# SCH_FMC-R2_MBOT_2026-02-22.net
KiCad netlist of a schematic drawn in EasyEDA
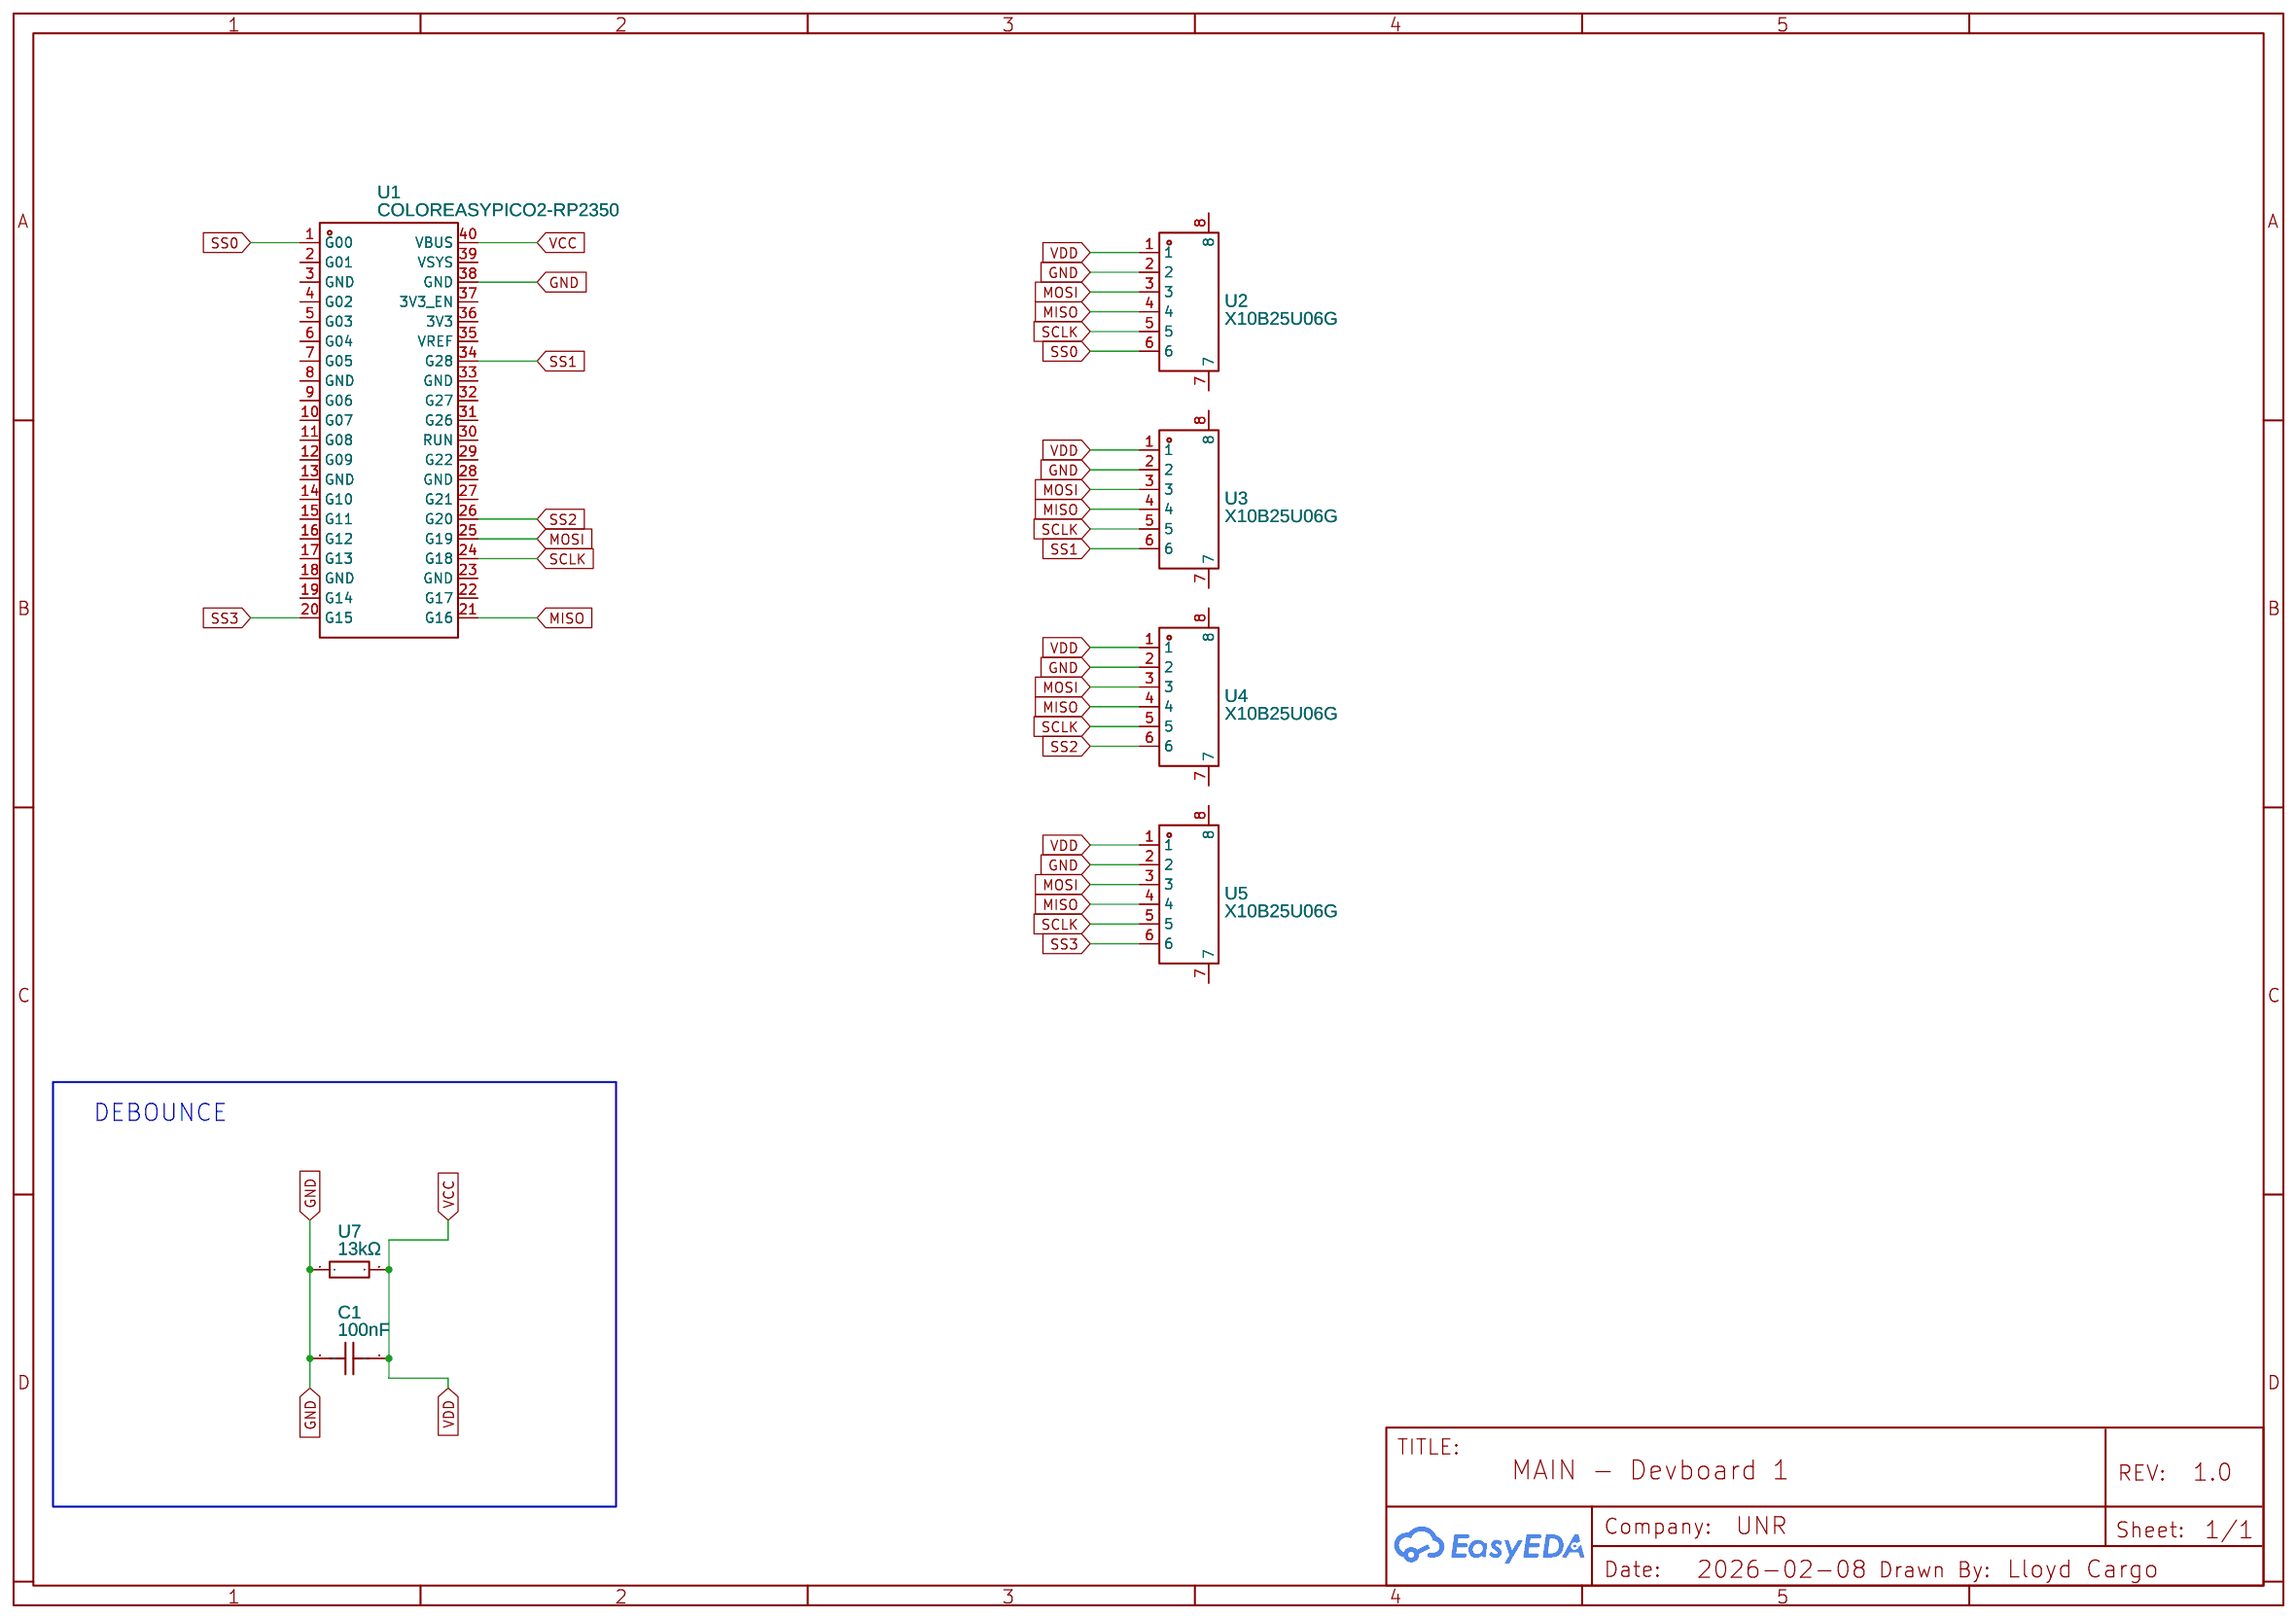
[diagram p0: MAIN]
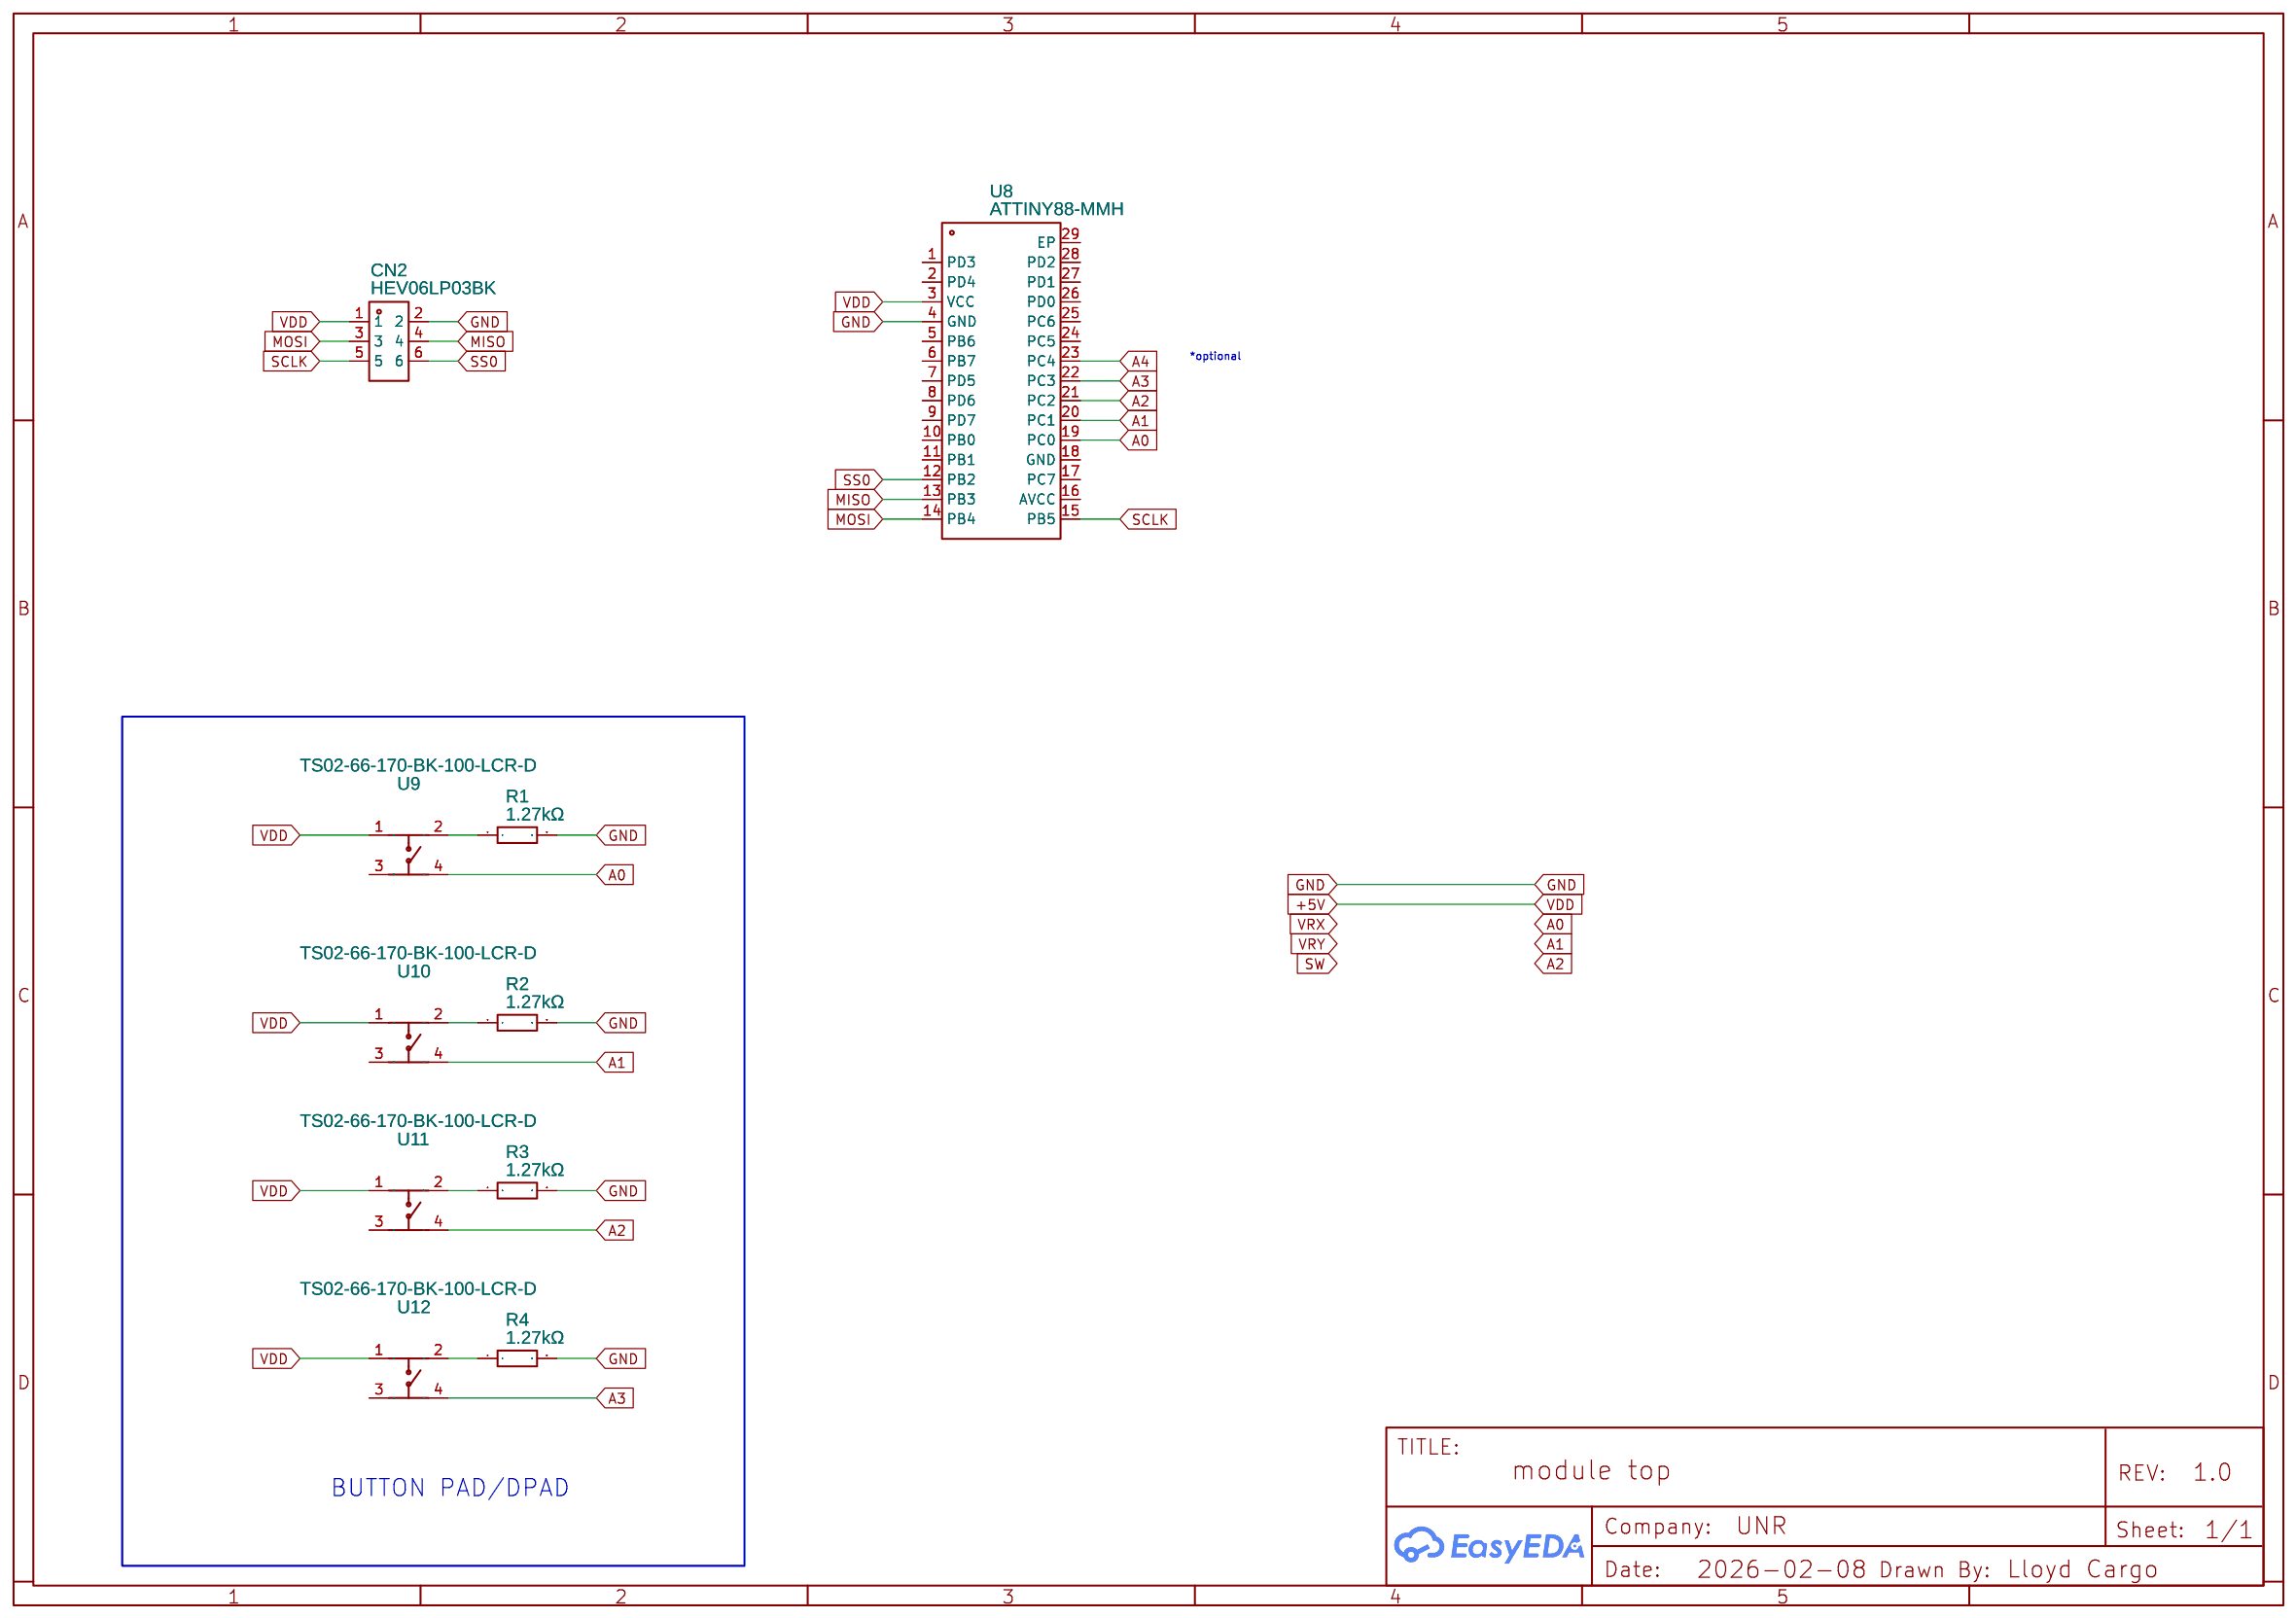
[diagram p1: module top]
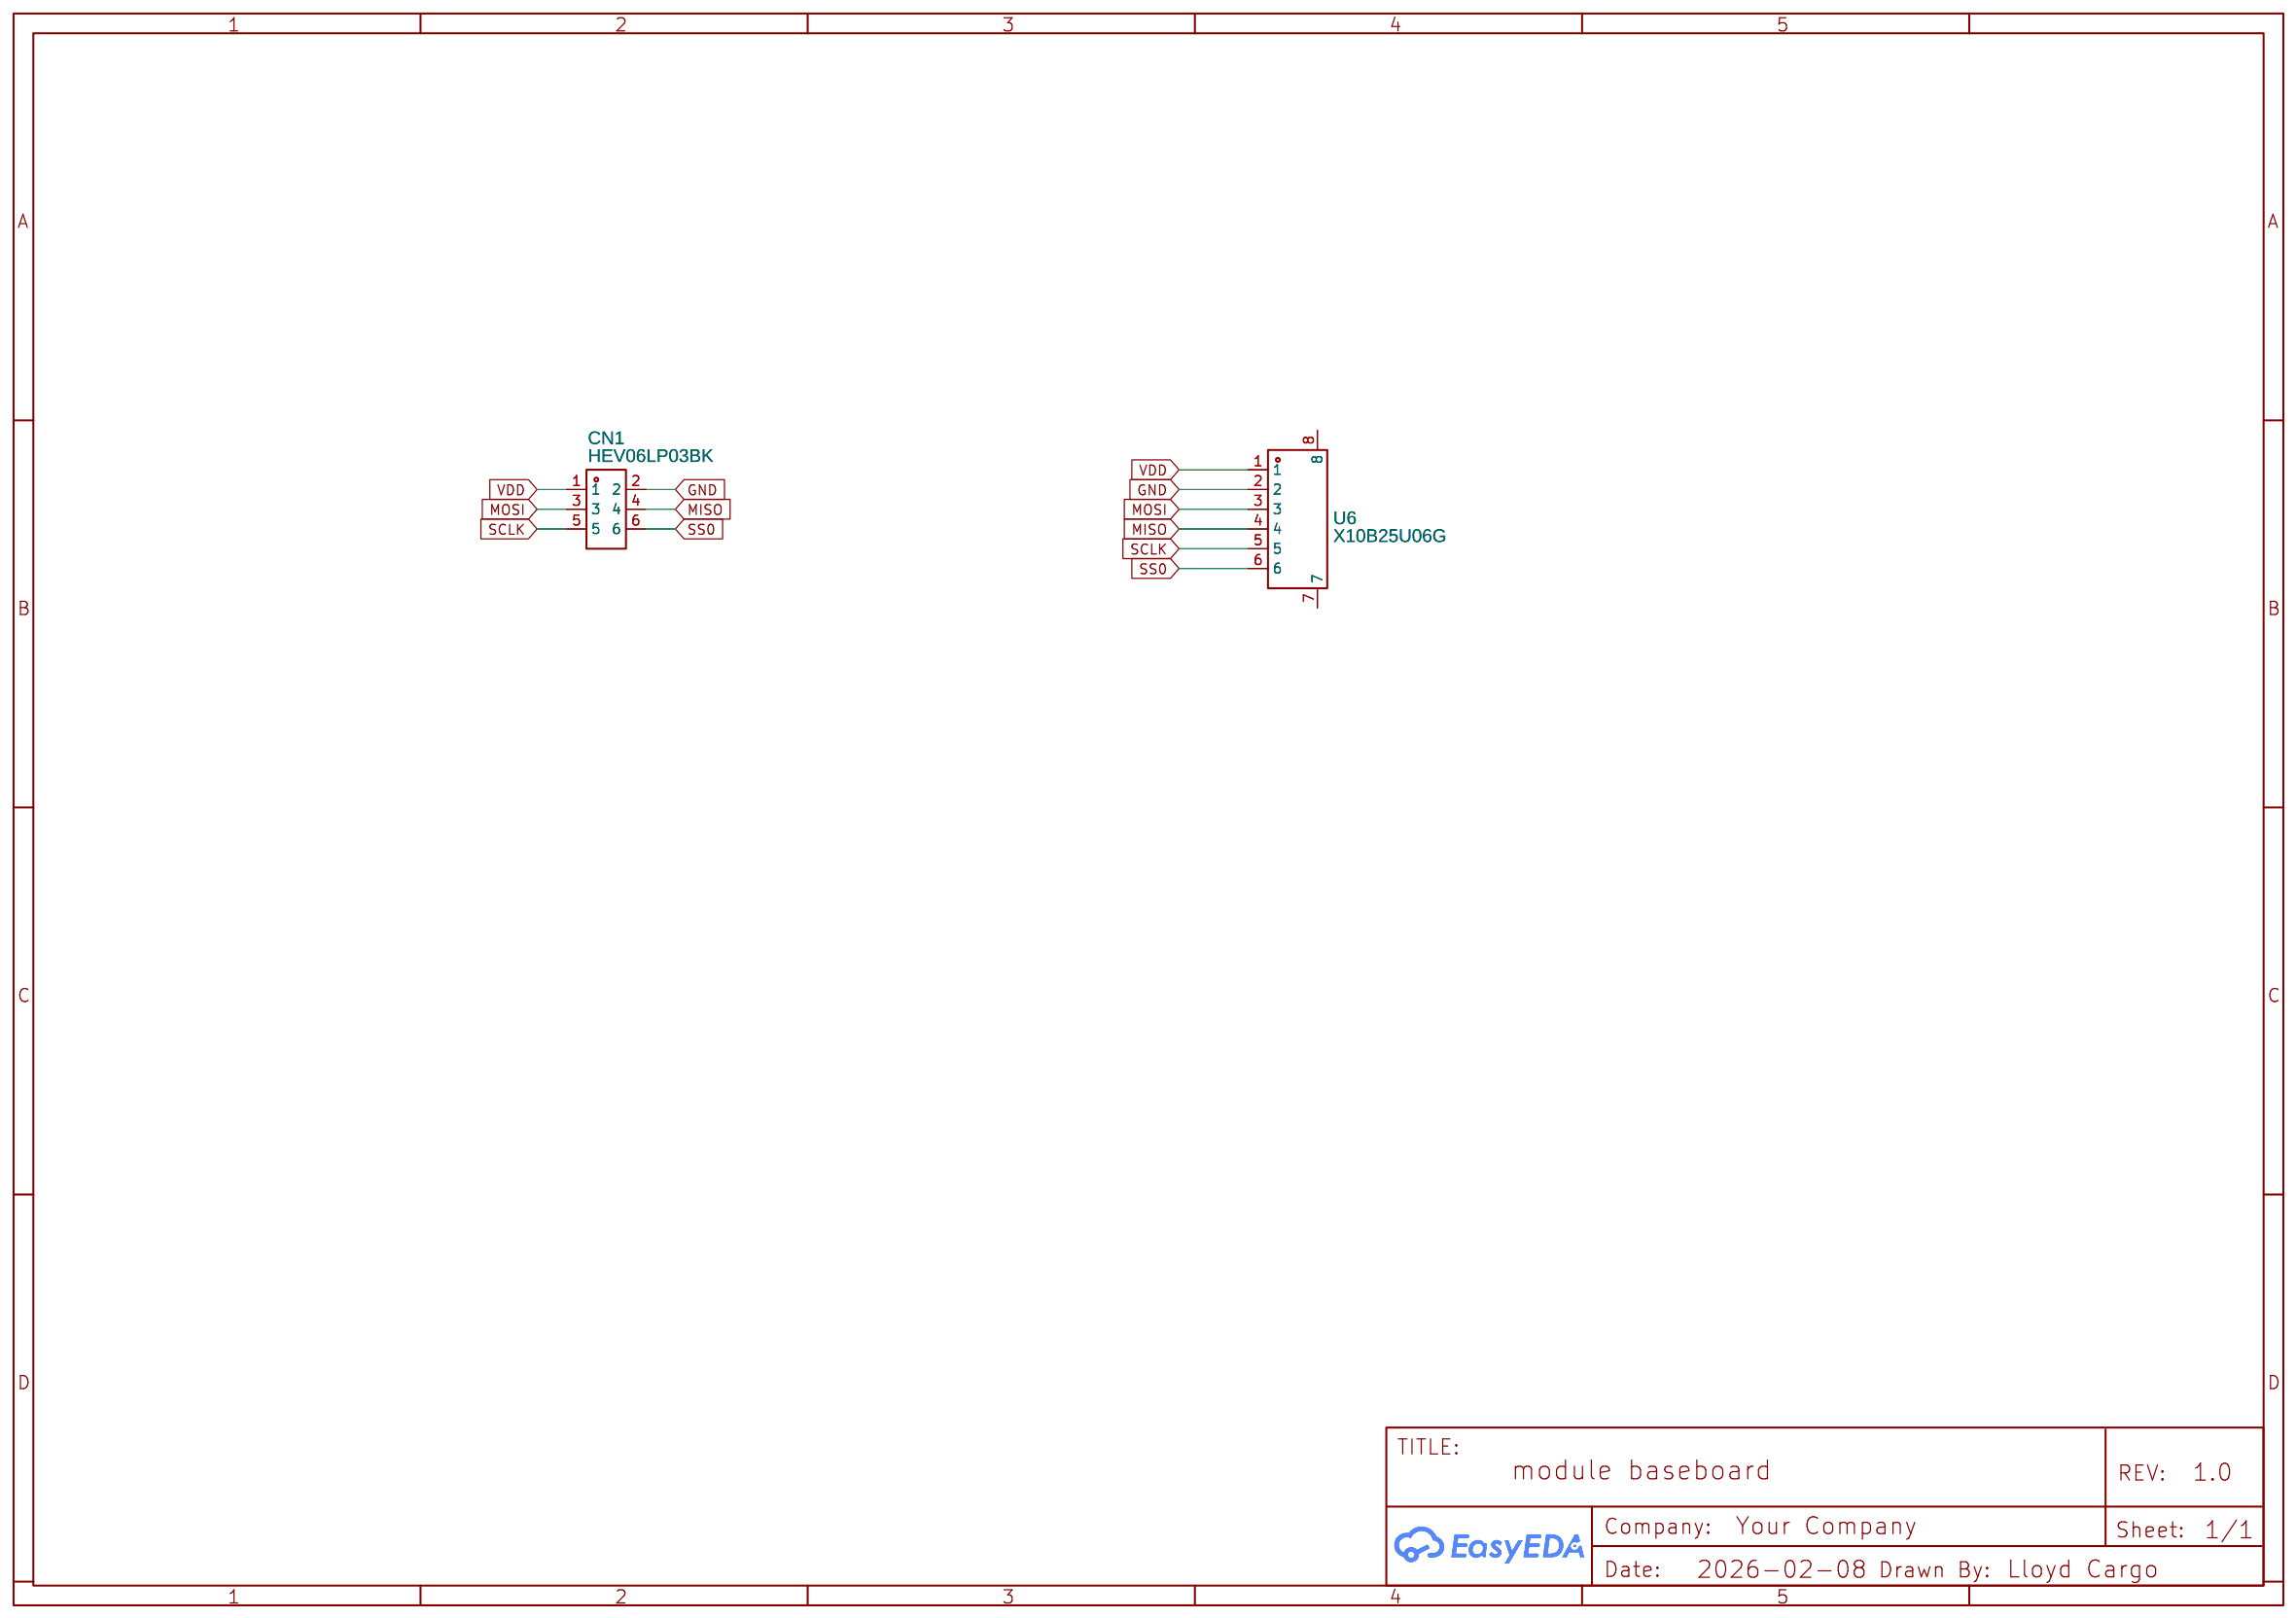
[diagram p2: module baseboard]

(export (version "E")
  (design (tool "Eeschema 10.0.6"))
  (components
    (comp (ref "C1")
      (value "100nF")
      (fields
        (field (name "Manufacturer Part") "GCG188R92A104KA03D")
        (field (name "Manufacturer") "muRata(村田)")
      )
      (libsource (lib "") (part "GCG188R92A104KA03D"))
    )
    (comp (ref "U1")
      (value "COLOREASYPICO2-RP2350")
      (fields
        (field (name "Manufacturer Part") "ColorEasyPico2-RP2350")
        (field (name "Manufacturer") "立创开发板")
      )
      (libsource (lib "") (part "COLOREASYPICO2-RP2350"))
    )
    (comp (ref "U2")
      (value "X10B25U06G")
      (fields (field (name "Manufacturer") "XKB Connection(中国星坤)"))
      (libsource (lib "") (part "X10B25U06G"))
    )
    (comp (ref "U3")
      (value "X10B25U06G")
      (fields (field (name "Manufacturer") "XKB Connection(中国星坤)"))
      (libsource (lib "") (part "X10B25U06G"))
    )
    (comp (ref "U4")
      (value "X10B25U06G")
      (fields (field (name "Manufacturer") "XKB Connection(中国星坤)"))
      (libsource (lib "") (part "X10B25U06G"))
    )
    (comp (ref "U5")
      (value "X10B25U06G")
      (fields (field (name "Manufacturer") "XKB Connection(中国星坤)"))
      (libsource (lib "") (part "X10B25U06G"))
    )
    (comp (ref "U7")
      (value "13kΩ")
      (fields (field (name "Manufacturer Part") "HPCR0805F13K0K9") (field (name "Manufacturer") "RESI(开步睿思)"))
      (libsource (lib "") (part "HPCR0805F13K0K9"))
    )
    (comp (ref "CN2")
      (value "HEV06LP03BK")
      (fields (field (name "Manufacturer") "WingTAT(格林柏)"))
      (libsource (lib "") (part "HEV06LP03BK"))
    )
    (comp (ref "R1")
      (value "1.27kΩ")
      (fields (field (name "Manufacturer Part") "RC0603FR-071K27L") (field (name "Manufacturer") "YAGEO(国巨)"))
      (libsource (lib "") (part "RC0603FR-071K27L"))
    )
    (comp (ref "R2")
      (value "1.27kΩ")
      (fields (field (name "Manufacturer Part") "RC0603FR-071K27L") (field (name "Manufacturer") "YAGEO(国巨)"))
      (libsource (lib "") (part "RC0603FR-071K27L"))
    )
    (comp (ref "R3")
      (value "1.27kΩ")
      (fields (field (name "Manufacturer Part") "RC0603FR-071K27L") (field (name "Manufacturer") "YAGEO(国巨)"))
      (libsource (lib "") (part "RC0603FR-071K27L"))
    )
    (comp (ref "R4")
      (value "1.27kΩ")
      (fields (field (name "Manufacturer Part") "RC0603FR-071K27L") (field (name "Manufacturer") "YAGEO(国巨)"))
      (libsource (lib "") (part "RC0603FR-071K27L"))
    )
    (comp (ref "U8")
      (value "ATTINY88-MMH")
      (fields (field (name "Manufacturer") "MICROCHIP(美国微芯)"))
      (libsource (lib "") (part "ATTINY88-MMH"))
    )
    (comp (ref "U9")
      (value "TS02-66-170-BK-100-LCR-D")
      (fields (field (name "Manufacturer") "CUI"))
      (libsource (lib "") (part "TS02-66-170-BK-100-LCR-D"))
    )
    (comp (ref "U10")
      (value "TS02-66-170-BK-100-LCR-D")
      (fields (field (name "Manufacturer") "CUI"))
      (libsource (lib "") (part "TS02-66-170-BK-100-LCR-D"))
    )
    (comp (ref "U11")
      (value "TS02-66-170-BK-100-LCR-D")
      (fields (field (name "Manufacturer") "CUI"))
      (libsource (lib "") (part "TS02-66-170-BK-100-LCR-D"))
    )
    (comp (ref "U12")
      (value "TS02-66-170-BK-100-LCR-D")
      (fields (field (name "Manufacturer") "CUI"))
      (libsource (lib "") (part "TS02-66-170-BK-100-LCR-D"))
    )
    (comp (ref "CN1")
      (value "HEV06LP03BK")
      (fields (field (name "Manufacturer") "WingTAT(格林柏)"))
      (libsource (lib "") (part "HEV06LP03BK"))
    )
    (comp (ref "U6")
      (value "X10B25U06G")
      (fields (field (name "Manufacturer") "XKB Connection(中国星坤)"))
      (libsource (lib "") (part "X10B25U06G"))
    )
  )
  (nets
    (net (code "1") (name "+5V") (class "Default")
      (node (ref "C1") (pin "2") (pinfunction "2_2") (pintype "unspecified"))
      (node (ref "CN1") (pin "1") (pinfunction "1_1") (pintype "unspecified"))
      (node (ref "CN2") (pin "1") (pinfunction "1_1") (pintype "unspecified"))
      (node (ref "U1") (pin "40") (pinfunction "VBUS_40") (pintype "unspecified"))
      (node (ref "U10") (pin "1") (pinfunction "1_1") (pintype "unspecified"))
      (node (ref "U11") (pin "1") (pinfunction "1_1") (pintype "unspecified"))
      (node (ref "U12") (pin "1") (pinfunction "1_1") (pintype "unspecified"))
      (node (ref "U2") (pin "1") (pinfunction "1_1") (pintype "unspecified"))
      (node (ref "U3") (pin "1") (pinfunction "1_1") (pintype "unspecified"))
      (node (ref "U4") (pin "1") (pinfunction "1_1") (pintype "unspecified"))
      (node (ref "U5") (pin "1") (pinfunction "1_1") (pintype "unspecified"))
      (node (ref "U6") (pin "1") (pinfunction "1_1") (pintype "unspecified"))
      (node (ref "U7") (pin "2") (pinfunction "2_2") (pintype "unspecified"))
      (node (ref "U8") (pin "3") (pinfunction "VCC_3") (pintype "unspecified"))
      (node (ref "U9") (pin "1") (pinfunction "1_1") (pintype "unspecified"))
    )
    (net (code "2") (name "A0") (class "Default")
      (node (ref "U8") (pin "19") (pinfunction "PC0_19") (pintype "unspecified"))
      (node (ref "U9") (pin "4") (pinfunction "4_4") (pintype "unspecified"))
    )
    (net (code "3") (name "A1") (class "Default")
      (node (ref "U10") (pin "4") (pinfunction "4_4") (pintype "unspecified"))
      (node (ref "U8") (pin "20") (pinfunction "PC1_20") (pintype "unspecified"))
    )
    (net (code "4") (name "A2") (class "Default")
      (node (ref "U11") (pin "4") (pinfunction "4_4") (pintype "unspecified"))
      (node (ref "U8") (pin "21") (pinfunction "PC2_21") (pintype "unspecified"))
    )
    (net (code "5") (name "A3") (class "Default")
      (node (ref "U12") (pin "4") (pinfunction "4_4") (pintype "unspecified"))
      (node (ref "U8") (pin "22") (pinfunction "PC3_22") (pintype "unspecified"))
    )
    (net (code "6") (name "A4") (class "Default")
      (node (ref "U8") (pin "23") (pinfunction "PC4_23") (pintype "unspecified"))
    )
    (net (code "7") (name "GND") (class "Default")
      (node (ref "C1") (pin "1") (pinfunction "1_1") (pintype "unspecified"))
      (node (ref "CN1") (pin "2") (pinfunction "2_2") (pintype "unspecified"))
      (node (ref "CN2") (pin "2") (pinfunction "2_2") (pintype "unspecified"))
      (node (ref "R1") (pin "2") (pinfunction "2_2") (pintype "unspecified"))
      (node (ref "R2") (pin "2") (pinfunction "2_2") (pintype "unspecified"))
      (node (ref "R3") (pin "2") (pinfunction "2_2") (pintype "unspecified"))
      (node (ref "R4") (pin "2") (pinfunction "2_2") (pintype "unspecified"))
      (node (ref "U1") (pin "38") (pinfunction "GND_38") (pintype "unspecified"))
      (node (ref "U2") (pin "2") (pinfunction "2_2") (pintype "unspecified"))
      (node (ref "U3") (pin "2") (pinfunction "2_2") (pintype "unspecified"))
      (node (ref "U4") (pin "2") (pinfunction "2_2") (pintype "unspecified"))
      (node (ref "U5") (pin "2") (pinfunction "2_2") (pintype "unspecified"))
      (node (ref "U6") (pin "2") (pinfunction "2_2") (pintype "unspecified"))
      (node (ref "U7") (pin "1") (pinfunction "1_1") (pintype "unspecified"))
      (node (ref "U8") (pin "4") (pinfunction "GND_4") (pintype "unspecified"))
    )
    (net (code "8") (name "MISO") (class "Default")
      (node (ref "CN1") (pin "4") (pinfunction "4_4") (pintype "unspecified"))
      (node (ref "CN2") (pin "4") (pinfunction "4_4") (pintype "unspecified"))
      (node (ref "U1") (pin "21") (pinfunction "G16_21") (pintype "unspecified"))
      (node (ref "U2") (pin "4") (pinfunction "4_4") (pintype "unspecified"))
      (node (ref "U3") (pin "4") (pinfunction "4_4") (pintype "unspecified"))
      (node (ref "U4") (pin "4") (pinfunction "4_4") (pintype "unspecified"))
      (node (ref "U5") (pin "4") (pinfunction "4_4") (pintype "unspecified"))
      (node (ref "U6") (pin "4") (pinfunction "4_4") (pintype "unspecified"))
      (node (ref "U8") (pin "13") (pinfunction "PB3_13") (pintype "unspecified"))
    )
    (net (code "9") (name "MOSI") (class "Default")
      (node (ref "CN1") (pin "3") (pinfunction "3_3") (pintype "unspecified"))
      (node (ref "CN2") (pin "3") (pinfunction "3_3") (pintype "unspecified"))
      (node (ref "U1") (pin "25") (pinfunction "G19_25") (pintype "unspecified"))
      (node (ref "U2") (pin "3") (pinfunction "3_3") (pintype "unspecified"))
      (node (ref "U3") (pin "3") (pinfunction "3_3") (pintype "unspecified"))
      (node (ref "U4") (pin "3") (pinfunction "3_3") (pintype "unspecified"))
      (node (ref "U5") (pin "3") (pinfunction "3_3") (pintype "unspecified"))
      (node (ref "U6") (pin "3") (pinfunction "3_3") (pintype "unspecified"))
      (node (ref "U8") (pin "14") (pinfunction "PB4_14") (pintype "unspecified"))
    )
    (net (code "10") (name "Net-(R1-Pad1)") (class "Default")
      (node (ref "R1") (pin "1") (pinfunction "1_1") (pintype "unspecified"))
      (node (ref "U9") (pin "2") (pinfunction "2_2") (pintype "unspecified"))
    )
    (net (code "11") (name "Net-(R2-Pad1)") (class "Default")
      (node (ref "R2") (pin "1") (pinfunction "1_1") (pintype "unspecified"))
      (node (ref "U10") (pin "2") (pinfunction "2_2") (pintype "unspecified"))
    )
    (net (code "12") (name "Net-(R3-Pad1)") (class "Default")
      (node (ref "R3") (pin "1") (pinfunction "1_1") (pintype "unspecified"))
      (node (ref "U11") (pin "2") (pinfunction "2_2") (pintype "unspecified"))
    )
    (net (code "13") (name "Net-(R4-Pad1)") (class "Default")
      (node (ref "R4") (pin "1") (pinfunction "1_1") (pintype "unspecified"))
      (node (ref "U12") (pin "2") (pinfunction "2_2") (pintype "unspecified"))
    )
    (net (code "14") (name "SCLK") (class "Default")
      (node (ref "CN1") (pin "5") (pinfunction "5_5") (pintype "unspecified"))
      (node (ref "CN2") (pin "5") (pinfunction "5_5") (pintype "unspecified"))
      (node (ref "U1") (pin "24") (pinfunction "G18_24") (pintype "unspecified"))
      (node (ref "U2") (pin "5") (pinfunction "5_5") (pintype "unspecified"))
      (node (ref "U3") (pin "5") (pinfunction "5_5") (pintype "unspecified"))
      (node (ref "U4") (pin "5") (pinfunction "5_5") (pintype "unspecified"))
      (node (ref "U5") (pin "5") (pinfunction "5_5") (pintype "unspecified"))
      (node (ref "U6") (pin "5") (pinfunction "5_5") (pintype "unspecified"))
      (node (ref "U8") (pin "15") (pinfunction "PB5_15") (pintype "unspecified"))
    )
    (net (code "15") (name "SS0") (class "Default")
      (node (ref "CN1") (pin "6") (pinfunction "6_6") (pintype "unspecified"))
      (node (ref "CN2") (pin "6") (pinfunction "6_6") (pintype "unspecified"))
      (node (ref "U1") (pin "1") (pinfunction "G00_1") (pintype "unspecified"))
      (node (ref "U2") (pin "6") (pinfunction "6_6") (pintype "unspecified"))
      (node (ref "U6") (pin "6") (pinfunction "6_6") (pintype "unspecified"))
      (node (ref "U8") (pin "12") (pinfunction "PB2_12") (pintype "unspecified"))
    )
    (net (code "16") (name "SS1") (class "Default")
      (node (ref "U1") (pin "34") (pinfunction "G28_34") (pintype "unspecified"))
      (node (ref "U3") (pin "6") (pinfunction "6_6") (pintype "unspecified"))
    )
    (net (code "17") (name "SS2") (class "Default")
      (node (ref "U1") (pin "26") (pinfunction "G20_26") (pintype "unspecified"))
      (node (ref "U4") (pin "6") (pinfunction "6_6") (pintype "unspecified"))
    )
    (net (code "18") (name "SS3") (class "Default")
      (node (ref "U1") (pin "20") (pinfunction "G15_20") (pintype "unspecified"))
      (node (ref "U5") (pin "6") (pinfunction "6_6") (pintype "unspecified"))
    )
    (net (code "22") (name "unconnected-(U1-3V3-Pad36)") (class "Default")
      (node (ref "U1") (pin "36") (pinfunction "3V3_36") (pintype "unspecified"))
    )
    (net (code "23") (name "unconnected-(U1-3V3_EN-Pad37)") (class "Default")
      (node (ref "U1") (pin "37") (pinfunction "3V3_EN_37") (pintype "unspecified"))
    )
    (net (code "24") (name "unconnected-(U1-G01-Pad2)") (class "Default")
      (node (ref "U1") (pin "2") (pinfunction "G01_2") (pintype "unspecified"))
    )
    (net (code "25") (name "unconnected-(U1-G02-Pad4)") (class "Default")
      (node (ref "U1") (pin "4") (pinfunction "G02_4") (pintype "unspecified"))
    )
    (net (code "26") (name "unconnected-(U1-G03-Pad5)") (class "Default")
      (node (ref "U1") (pin "5") (pinfunction "G03_5") (pintype "unspecified"))
    )
    (net (code "27") (name "unconnected-(U1-G04-Pad6)") (class "Default")
      (node (ref "U1") (pin "6") (pinfunction "G04_6") (pintype "unspecified"))
    )
    (net (code "28") (name "unconnected-(U1-G05-Pad7)") (class "Default")
      (node (ref "U1") (pin "7") (pinfunction "G05_7") (pintype "unspecified"))
    )
    (net (code "29") (name "unconnected-(U1-G06-Pad9)") (class "Default")
      (node (ref "U1") (pin "9") (pinfunction "G06_9") (pintype "unspecified"))
    )
    (net (code "30") (name "unconnected-(U1-G07-Pad10)") (class "Default")
      (node (ref "U1") (pin "10") (pinfunction "G07_10") (pintype "unspecified"))
    )
    (net (code "31") (name "unconnected-(U1-G08-Pad11)") (class "Default")
      (node (ref "U1") (pin "11") (pinfunction "G08_11") (pintype "unspecified"))
    )
    (net (code "32") (name "unconnected-(U1-G09-Pad12)") (class "Default")
      (node (ref "U1") (pin "12") (pinfunction "G09_12") (pintype "unspecified"))
    )
    (net (code "33") (name "unconnected-(U1-G10-Pad14)") (class "Default")
      (node (ref "U1") (pin "14") (pinfunction "G10_14") (pintype "unspecified"))
    )
    (net (code "34") (name "unconnected-(U1-G11-Pad15)") (class "Default")
      (node (ref "U1") (pin "15") (pinfunction "G11_15") (pintype "unspecified"))
    )
    (net (code "35") (name "unconnected-(U1-G12-Pad16)") (class "Default")
      (node (ref "U1") (pin "16") (pinfunction "G12_16") (pintype "unspecified"))
    )
    (net (code "36") (name "unconnected-(U1-G13-Pad17)") (class "Default")
      (node (ref "U1") (pin "17") (pinfunction "G13_17") (pintype "unspecified"))
    )
    (net (code "37") (name "unconnected-(U1-G14-Pad19)") (class "Default")
      (node (ref "U1") (pin "19") (pinfunction "G14_19") (pintype "unspecified"))
    )
    (net (code "38") (name "unconnected-(U1-G17-Pad22)") (class "Default")
      (node (ref "U1") (pin "22") (pinfunction "G17_22") (pintype "unspecified"))
    )
    (net (code "39") (name "unconnected-(U1-G21-Pad27)") (class "Default")
      (node (ref "U1") (pin "27") (pinfunction "G21_27") (pintype "unspecified"))
    )
    (net (code "40") (name "unconnected-(U1-G22-Pad29)") (class "Default")
      (node (ref "U1") (pin "29") (pinfunction "G22_29") (pintype "unspecified"))
    )
    (net (code "41") (name "unconnected-(U1-G26-Pad31)") (class "Default")
      (node (ref "U1") (pin "31") (pinfunction "G26_31") (pintype "unspecified"))
    )
    (net (code "42") (name "unconnected-(U1-G27-Pad32)") (class "Default")
      (node (ref "U1") (pin "32") (pinfunction "G27_32") (pintype "unspecified"))
    )
    (net (code "43") (name "unconnected-(U1-GND-Pad3)") (class "Default")
      (node (ref "U1") (pin "3") (pinfunction "GND_3") (pintype "unspecified"))
    )
    (net (code "44") (name "unconnected-(U1-GND-Pad8)") (class "Default")
      (node (ref "U1") (pin "8") (pinfunction "GND_8") (pintype "unspecified"))
    )
    (net (code "45") (name "unconnected-(U1-GND-Pad13)") (class "Default")
      (node (ref "U1") (pin "13") (pinfunction "GND_13") (pintype "unspecified"))
    )
    (net (code "46") (name "unconnected-(U1-GND-Pad18)") (class "Default")
      (node (ref "U1") (pin "18") (pinfunction "GND_18") (pintype "unspecified"))
    )
    (net (code "47") (name "unconnected-(U1-GND-Pad23)") (class "Default")
      (node (ref "U1") (pin "23") (pinfunction "GND_23") (pintype "unspecified"))
    )
    (net (code "48") (name "unconnected-(U1-GND-Pad28)") (class "Default")
      (node (ref "U1") (pin "28") (pinfunction "GND_28") (pintype "unspecified"))
    )
    (net (code "49") (name "unconnected-(U1-GND-Pad33)") (class "Default")
      (node (ref "U1") (pin "33") (pinfunction "GND_33") (pintype "unspecified"))
    )
    (net (code "50") (name "unconnected-(U1-RUN-Pad30)") (class "Default")
      (node (ref "U1") (pin "30") (pinfunction "RUN_30") (pintype "unspecified"))
    )
    (net (code "51") (name "unconnected-(U1-VREF-Pad35)") (class "Default")
      (node (ref "U1") (pin "35") (pinfunction "VREF_35") (pintype "unspecified"))
    )
    (net (code "52") (name "unconnected-(U1-VSYS-Pad39)") (class "Default")
      (node (ref "U1") (pin "39") (pinfunction "VSYS_39") (pintype "unspecified"))
    )
    (net (code "53") (name "unconnected-(U2-Pad7)") (class "Default")
      (node (ref "U2") (pin "7") (pinfunction "7_7") (pintype "unspecified"))
    )
    (net (code "54") (name "unconnected-(U2-Pad8)") (class "Default")
      (node (ref "U2") (pin "8") (pinfunction "8_8") (pintype "unspecified"))
    )
    (net (code "55") (name "unconnected-(U3-Pad7)") (class "Default")
      (node (ref "U3") (pin "7") (pinfunction "7_7") (pintype "unspecified"))
    )
    (net (code "56") (name "unconnected-(U3-Pad8)") (class "Default")
      (node (ref "U3") (pin "8") (pinfunction "8_8") (pintype "unspecified"))
    )
    (net (code "57") (name "unconnected-(U4-Pad7)") (class "Default")
      (node (ref "U4") (pin "7") (pinfunction "7_7") (pintype "unspecified"))
    )
    (net (code "58") (name "unconnected-(U4-Pad8)") (class "Default")
      (node (ref "U4") (pin "8") (pinfunction "8_8") (pintype "unspecified"))
    )
    (net (code "59") (name "unconnected-(U5-Pad7)") (class "Default")
      (node (ref "U5") (pin "7") (pinfunction "7_7") (pintype "unspecified"))
    )
    (net (code "60") (name "unconnected-(U5-Pad8)") (class "Default")
      (node (ref "U5") (pin "8") (pinfunction "8_8") (pintype "unspecified"))
    )
    (net (code "61") (name "unconnected-(U6-Pad7)") (class "Default")
      (node (ref "U6") (pin "7") (pinfunction "7_7") (pintype "unspecified"))
    )
    (net (code "62") (name "unconnected-(U6-Pad8)") (class "Default")
      (node (ref "U6") (pin "8") (pinfunction "8_8") (pintype "unspecified"))
    )
    (net (code "63") (name "unconnected-(U8-AVCC-Pad16)") (class "Default")
      (node (ref "U8") (pin "16") (pinfunction "AVCC_16") (pintype "unspecified"))
    )
    (net (code "64") (name "unconnected-(U8-EP-Pad29)") (class "Default")
      (node (ref "U8") (pin "29") (pinfunction "EP_29") (pintype "unspecified"))
    )
    (net (code "65") (name "unconnected-(U8-GND-Pad18)") (class "Default")
      (node (ref "U8") (pin "18") (pinfunction "GND_18") (pintype "unspecified"))
    )
    (net (code "66") (name "unconnected-(U8-PB0-Pad10)") (class "Default")
      (node (ref "U8") (pin "10") (pinfunction "PB0_10") (pintype "unspecified"))
    )
    (net (code "67") (name "unconnected-(U8-PB1-Pad11)") (class "Default")
      (node (ref "U8") (pin "11") (pinfunction "PB1_11") (pintype "unspecified"))
    )
    (net (code "68") (name "unconnected-(U8-PB6-Pad5)") (class "Default")
      (node (ref "U8") (pin "5") (pinfunction "PB6_5") (pintype "unspecified"))
    )
    (net (code "69") (name "unconnected-(U8-PB7-Pad6)") (class "Default")
      (node (ref "U8") (pin "6") (pinfunction "PB7_6") (pintype "unspecified"))
    )
    (net (code "70") (name "unconnected-(U8-PC5-Pad24)") (class "Default")
      (node (ref "U8") (pin "24") (pinfunction "PC5_24") (pintype "unspecified"))
    )
    (net (code "71") (name "unconnected-(U8-PC6-Pad25)") (class "Default")
      (node (ref "U8") (pin "25") (pinfunction "PC6_25") (pintype "unspecified"))
    )
    (net (code "72") (name "unconnected-(U8-PC7-Pad17)") (class "Default")
      (node (ref "U8") (pin "17") (pinfunction "PC7_17") (pintype "unspecified"))
    )
    (net (code "73") (name "unconnected-(U8-PD0-Pad26)") (class "Default")
      (node (ref "U8") (pin "26") (pinfunction "PD0_26") (pintype "unspecified"))
    )
    (net (code "74") (name "unconnected-(U8-PD1-Pad27)") (class "Default")
      (node (ref "U8") (pin "27") (pinfunction "PD1_27") (pintype "unspecified"))
    )
    (net (code "75") (name "unconnected-(U8-PD2-Pad28)") (class "Default")
      (node (ref "U8") (pin "28") (pinfunction "PD2_28") (pintype "unspecified"))
    )
    (net (code "76") (name "unconnected-(U8-PD3-Pad1)") (class "Default")
      (node (ref "U8") (pin "1") (pinfunction "PD3_1") (pintype "unspecified"))
    )
    (net (code "77") (name "unconnected-(U8-PD4-Pad2)") (class "Default")
      (node (ref "U8") (pin "2") (pinfunction "PD4_2") (pintype "unspecified"))
    )
    (net (code "78") (name "unconnected-(U8-PD5-Pad7)") (class "Default")
      (node (ref "U8") (pin "7") (pinfunction "PD5_7") (pintype "unspecified"))
    )
    (net (code "79") (name "unconnected-(U8-PD6-Pad8)") (class "Default")
      (node (ref "U8") (pin "8") (pinfunction "PD6_8") (pintype "unspecified"))
    )
    (net (code "80") (name "unconnected-(U8-PD7-Pad9)") (class "Default")
      (node (ref "U8") (pin "9") (pinfunction "PD7_9") (pintype "unspecified"))
    )
    (net (code "81") (name "unconnected-(U9-Pad3)") (class "Default")
      (node (ref "U9") (pin "3") (pinfunction "3_3") (pintype "unspecified"))
    )
    (net (code "82") (name "unconnected-(U10-Pad3)") (class "Default")
      (node (ref "U10") (pin "3") (pinfunction "3_3") (pintype "unspecified"))
    )
    (net (code "83") (name "unconnected-(U11-Pad3)") (class "Default")
      (node (ref "U11") (pin "3") (pinfunction "3_3") (pintype "unspecified"))
    )
    (net (code "84") (name "unconnected-(U12-Pad3)") (class "Default")
      (node (ref "U12") (pin "3") (pinfunction "3_3") (pintype "unspecified"))
    )
  )
)
